# Power.net
KiCad netlist of a schematic drawn in Altium Designer
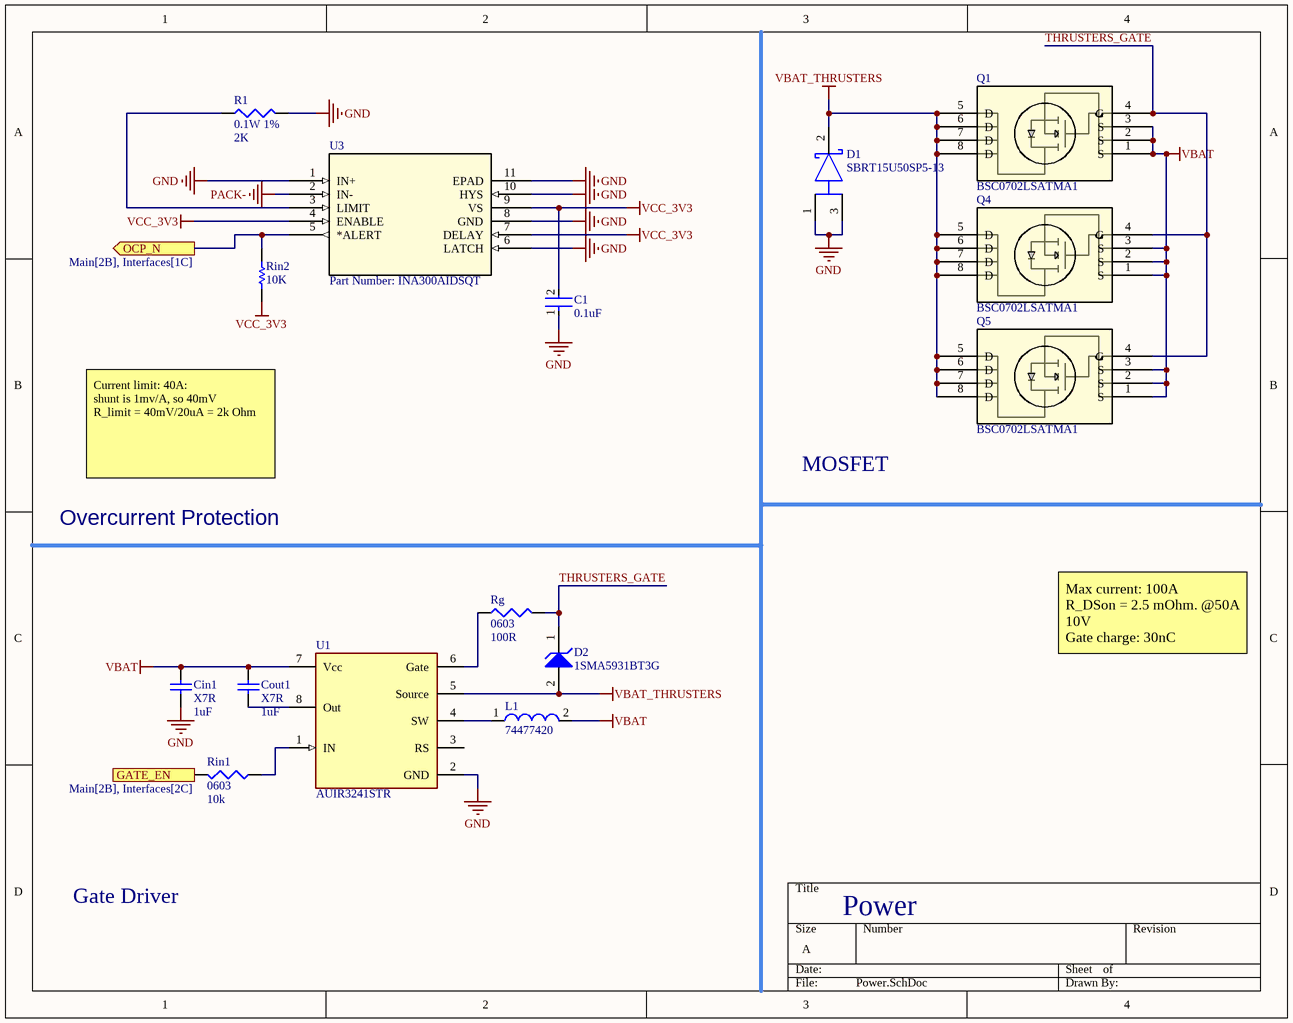
[diagram p0: Power.SchDoc]

(export (version "E")
  (design (tool "Eeschema 10.0.6"))
  (components
    (comp (ref "C1")
      (value "0.1uF")
      (footprint "FP-C0603C-CF-MFG")
      (description "CAP CER 0.1UF 10V X7R 0603")
      (fields (field (name "TOLERANCE") "0.1") (field (name "MANUFACTURER PART NUMBER") "C0603C104K8RACTU"))
      (libsource (lib "Altium Content Vault") (part "b4654b650e69147ec39a6b967a45e02"))
    )
    (comp (ref "Cin1")
      (value "X7R")
      (footprint "C0805")
      (description "Capacitor")
      (fields (field (name "ALTIUM_VALUE") "1uF") (field (name "PUBLISHER") "Altium Limited"))
      (libsource (lib "Miscellaneous Devices") (part "Cap"))
    )
    (comp (ref "Cout1")
      (value "X7R")
      (footprint "C0805")
      (description "Capacitor")
      (fields (field (name "ALTIUM_VALUE") "1uF") (field (name "PUBLISHER") "Altium Limited"))
      (libsource (lib "Miscellaneous Devices") (part "Cap"))
    )
    (comp (ref "D1")
      (value "SBRT15U50SP5-13")
      (footprint "FP-PowerDI5-MFG")
      (description "50V 15A Rectifier Schottky Diode")
      (fields
        (field (name "OCTOPART") "https://octopart.com/pds3200-13-diodes+inc.-332544")
        (field (name "MANUFACTURER") "Diodes Inc.")
      )
      (libsource (lib "Altium Content Vault") (part "0222f6c3f9f8f3c07decc49f824026a"))
    )
    (comp (ref "D2")
      (value "1SMA5931BT3G")
      (footprint "ONSC-SMA-2-403D-02_F_V")
      (description "1.5 W Zener Voltage Regulator, 2-Pin SMA, Pb-Free, Tape and Reel")
      (fields (field (name "MANUFACTURER") "On Semiconductor"))
      (libsource (lib "Altium Content Vault") (part "ONSC-K1A2-2"))
    )
    (comp (ref "L1")
      (value "74477420")
      (footprint "WE-PD2-M")
      (description "SMD Power Inductor WE-PD2, L = 100 µH")
      (libsource (lib "Altium Content Vault") (part "PAS-IND-INDUCTOR-2"))
    )
    (comp (ref "Q1")
      (value "BSC0702LSATMA1")
      (footprint "PG-TDSON-8-7")
      (description "No Description Available")
      (libsource (lib "TAUV-Lib") (part "BSC0702LSATMA1"))
    )
    (comp (ref "Q4")
      (value "BSC0702LSATMA1")
      (footprint "PG-TDSON-8-7")
      (description "No Description Available")
      (libsource (lib "TAUV-Lib") (part "BSC0702LSATMA1"))
    )
    (comp (ref "Q5")
      (value "BSC0702LSATMA1")
      (footprint "PG-TDSON-8-7")
      (description "No Description Available")
      (libsource (lib "TAUV-Lib") (part "BSC0702LSATMA1"))
    )
    (comp (ref "R1")
      (value "0.1W 1%")
      (footprint "J1-0603")
      (description "2k 0.1W 1%")
      (fields (field (name "ALTIUM_VALUE") "2K") (field (name "PUBLISHER") "Altium Limited"))
      (libsource (lib "Miscellaneous Devices") (part "Res3"))
    )
    (comp (ref "Rg")
      (value "0603")
      (footprint "J1-0603")
      (description "Resistor")
      (fields (field (name "ALTIUM_VALUE") "100R") (field (name "PUBLISHER") "Altium Limited"))
      (libsource (lib "Miscellaneous Devices") (part "Res3"))
    )
    (comp (ref "Rin1")
      (value "0603")
      (footprint "J1-0603")
      (description "Resistor")
      (fields (field (name "ALTIUM_VALUE") "10k") (field (name "PUBLISHER") "Altium Limited"))
      (libsource (lib "Miscellaneous Devices") (part "Res3"))
    )
    (comp (ref "Rin2")
      (value "10K")
      (footprint "RESC0603(1608)_N")
      (description "10K 0.1W 5% 0603 (1608 Metric)  SMD")
      (fields (field (name "TOLERANCE") "5 %") (field (name "POWER") "0.1 W"))
      (libsource (lib "Altium Content Vault") (part "RES"))
    )
    (comp (ref "U1")
      (value "AUIR3241STR")
      (footprint "FP-PG-DSO-8-MFG")
      (description "IC GATE DRVR HIGH-SIDE 8SO")
      (libsource (lib "Altium Content Vault") (part "34ae5cb6024c322bdcbf0313f74d293"))
    )
    (comp (ref "U3")
      (value "Part Number: INA300AIDSQT")
      (footprint "DSQ10_P9X1P5")
      (description "No Description Available")
      (fields
        (field (name "MANUFACTURER_PART_NUMBER") "INA300AIDSQT")
        (field (name "COPYRIGHT") "Copyright (C) 2018 Accelerated Designs. All rights reserved")
      )
      (libsource (lib "Tauv-Lib") (part "INA300AIDSQT"))
    )
  )
  (nets
    (net (code "1") (name "/GATE_EN") (class "Default")
      (node (ref "Rin1") (pin "2") (pinfunction "2_2") (pintype "passive"))
    )
    (net (code "2") (name "/OCP_N") (class "Default")
      (node (ref "Rin2") (pin "1") (pinfunction "1_1") (pintype "passive"))
      (node (ref "U3") (pin "5") (pinfunction "*ALERT_5") (pintype "output"))
    )
    (net (code "3") (name "/THRUSTERS_GATE") (class "Default")
      (node (ref "D2") (pin "1") (pinfunction "K_1") (pintype "passive"))
      (node (ref "Q1") (pin "4") (pinfunction "G_4") (pintype "passive"))
      (node (ref "Q4") (pin "4") (pinfunction "G_4") (pintype "passive"))
      (node (ref "Q5") (pin "4") (pinfunction "G_4") (pintype "passive"))
      (node (ref "Rg") (pin "2") (pinfunction "2_2") (pintype "passive"))
    )
    (net (code "4") (name "GND") (class "Default")
      (node (ref "C1") (pin "1") (pinfunction "1_1") (pintype "passive"))
      (node (ref "Cin1") (pin "1") (pinfunction "1_1") (pintype "passive"))
      (node (ref "D1") (pin "1") (pinfunction "A_1") (pintype "passive"))
      (node (ref "D1") (pin "3") (pinfunction "A_3") (pintype "passive"))
      (node (ref "R1") (pin "2") (pinfunction "2_2") (pintype "passive"))
      (node (ref "U1") (pin "2") (pinfunction "GND_2") (pintype "power_in"))
      (node (ref "U3") (pin "1") (pinfunction "IN+_1") (pintype "input"))
      (node (ref "U3") (pin "10") (pinfunction "HYS_10") (pintype "input"))
      (node (ref "U3") (pin "11") (pinfunction "EPAD_11") (pintype "passive"))
      (node (ref "U3") (pin "6") (pinfunction "LATCH_6") (pintype "input"))
      (node (ref "U3") (pin "8") (pinfunction "GND_8") (pintype "power_in"))
    )
    (net (code "5") (name "Net-(U1-Gate)") (class "Default")
      (node (ref "Rg") (pin "1") (pinfunction "1_1") (pintype "passive"))
      (node (ref "U1") (pin "6") (pinfunction "Gate_6") (pintype "passive"))
    )
    (net (code "6") (name "Net-(U1-IN)") (class "Default")
      (node (ref "Rin1") (pin "1") (pinfunction "1_1") (pintype "passive"))
      (node (ref "U1") (pin "1") (pinfunction "IN_1") (pintype "input"))
    )
    (net (code "7") (name "Net-(U1-Out)") (class "Default")
      (node (ref "Cout1") (pin "1") (pinfunction "1_1") (pintype "passive"))
      (node (ref "U1") (pin "8") (pinfunction "Out_8") (pintype "passive"))
    )
    (net (code "8") (name "Net-(U1-SW)") (class "Default")
      (node (ref "L1") (pin "1") (pinfunction "1_1") (pintype "passive"))
      (node (ref "U1") (pin "4") (pinfunction "SW_4") (pintype "passive"))
    )
    (net (code "9") (name "Net-(U3-LIMIT)") (class "Default")
      (node (ref "R1") (pin "1") (pinfunction "1_1") (pintype "passive"))
      (node (ref "U3") (pin "3") (pinfunction "LIMIT_3") (pintype "input"))
    )
    (net (code "10") (name "PACK-") (class "Default")
      (node (ref "U3") (pin "2") (pinfunction "IN-_2") (pintype "input"))
    )
    (net (code "11") (name "VBAT") (class "Default")
      (node (ref "Cin1") (pin "2") (pinfunction "2_2") (pintype "passive"))
      (node (ref "Cout1") (pin "2") (pinfunction "2_2") (pintype "passive"))
      (node (ref "L1") (pin "2") (pinfunction "2_2") (pintype "passive"))
      (node (ref "Q1") (pin "1") (pinfunction "S_1") (pintype "passive"))
      (node (ref "Q1") (pin "2") (pinfunction "S_2") (pintype "passive"))
      (node (ref "Q1") (pin "3") (pinfunction "S_3") (pintype "passive"))
      (node (ref "Q4") (pin "1") (pinfunction "S_1") (pintype "passive"))
      (node (ref "Q4") (pin "2") (pinfunction "S_2") (pintype "passive"))
      (node (ref "Q4") (pin "3") (pinfunction "S_3") (pintype "passive"))
      (node (ref "Q5") (pin "1") (pinfunction "S_1") (pintype "passive"))
      (node (ref "Q5") (pin "2") (pinfunction "S_2") (pintype "passive"))
      (node (ref "Q5") (pin "3") (pinfunction "S_3") (pintype "passive"))
      (node (ref "U1") (pin "7") (pinfunction "Vcc_7") (pintype "power_in"))
    )
    (net (code "12") (name "VBAT_THRUSTERS") (class "Default")
      (node (ref "D1") (pin "2") (pinfunction "C_2") (pintype "passive"))
      (node (ref "D2") (pin "2") (pinfunction "A_2") (pintype "passive"))
      (node (ref "Q1") (pin "5") (pinfunction "D_5") (pintype "passive"))
      (node (ref "Q1") (pin "6") (pinfunction "D_6") (pintype "passive"))
      (node (ref "Q1") (pin "7") (pinfunction "D_7") (pintype "passive"))
      (node (ref "Q1") (pin "8") (pinfunction "D_8") (pintype "passive"))
      (node (ref "Q4") (pin "5") (pinfunction "D_5") (pintype "passive"))
      (node (ref "Q4") (pin "6") (pinfunction "D_6") (pintype "passive"))
      (node (ref "Q4") (pin "7") (pinfunction "D_7") (pintype "passive"))
      (node (ref "Q4") (pin "8") (pinfunction "D_8") (pintype "passive"))
      (node (ref "Q5") (pin "5") (pinfunction "D_5") (pintype "passive"))
      (node (ref "Q5") (pin "6") (pinfunction "D_6") (pintype "passive"))
      (node (ref "Q5") (pin "7") (pinfunction "D_7") (pintype "passive"))
      (node (ref "Q5") (pin "8") (pinfunction "D_8") (pintype "passive"))
      (node (ref "U1") (pin "5") (pinfunction "Source_5") (pintype "passive"))
    )
    (net (code "13") (name "VCC_3V3") (class "Default")
      (node (ref "C1") (pin "2") (pinfunction "2_2") (pintype "passive"))
      (node (ref "Rin2") (pin "2") (pinfunction "2_2") (pintype "passive"))
      (node (ref "U3") (pin "4") (pinfunction "ENABLE_4") (pintype "input"))
      (node (ref "U3") (pin "7") (pinfunction "DELAY_7") (pintype "input"))
      (node (ref "U3") (pin "9") (pinfunction "VS_9") (pintype "power_in"))
    )
    (net (code "14") (name "unconnected-(U1-RS-Pad3)") (class "Default")
      (node (ref "U1") (pin "3") (pinfunction "RS_3") (pintype "passive"))
    )
  )
)
